# 4_Ethernet_PHY.net
KiCad netlist of a schematic drawn in Altium Designer
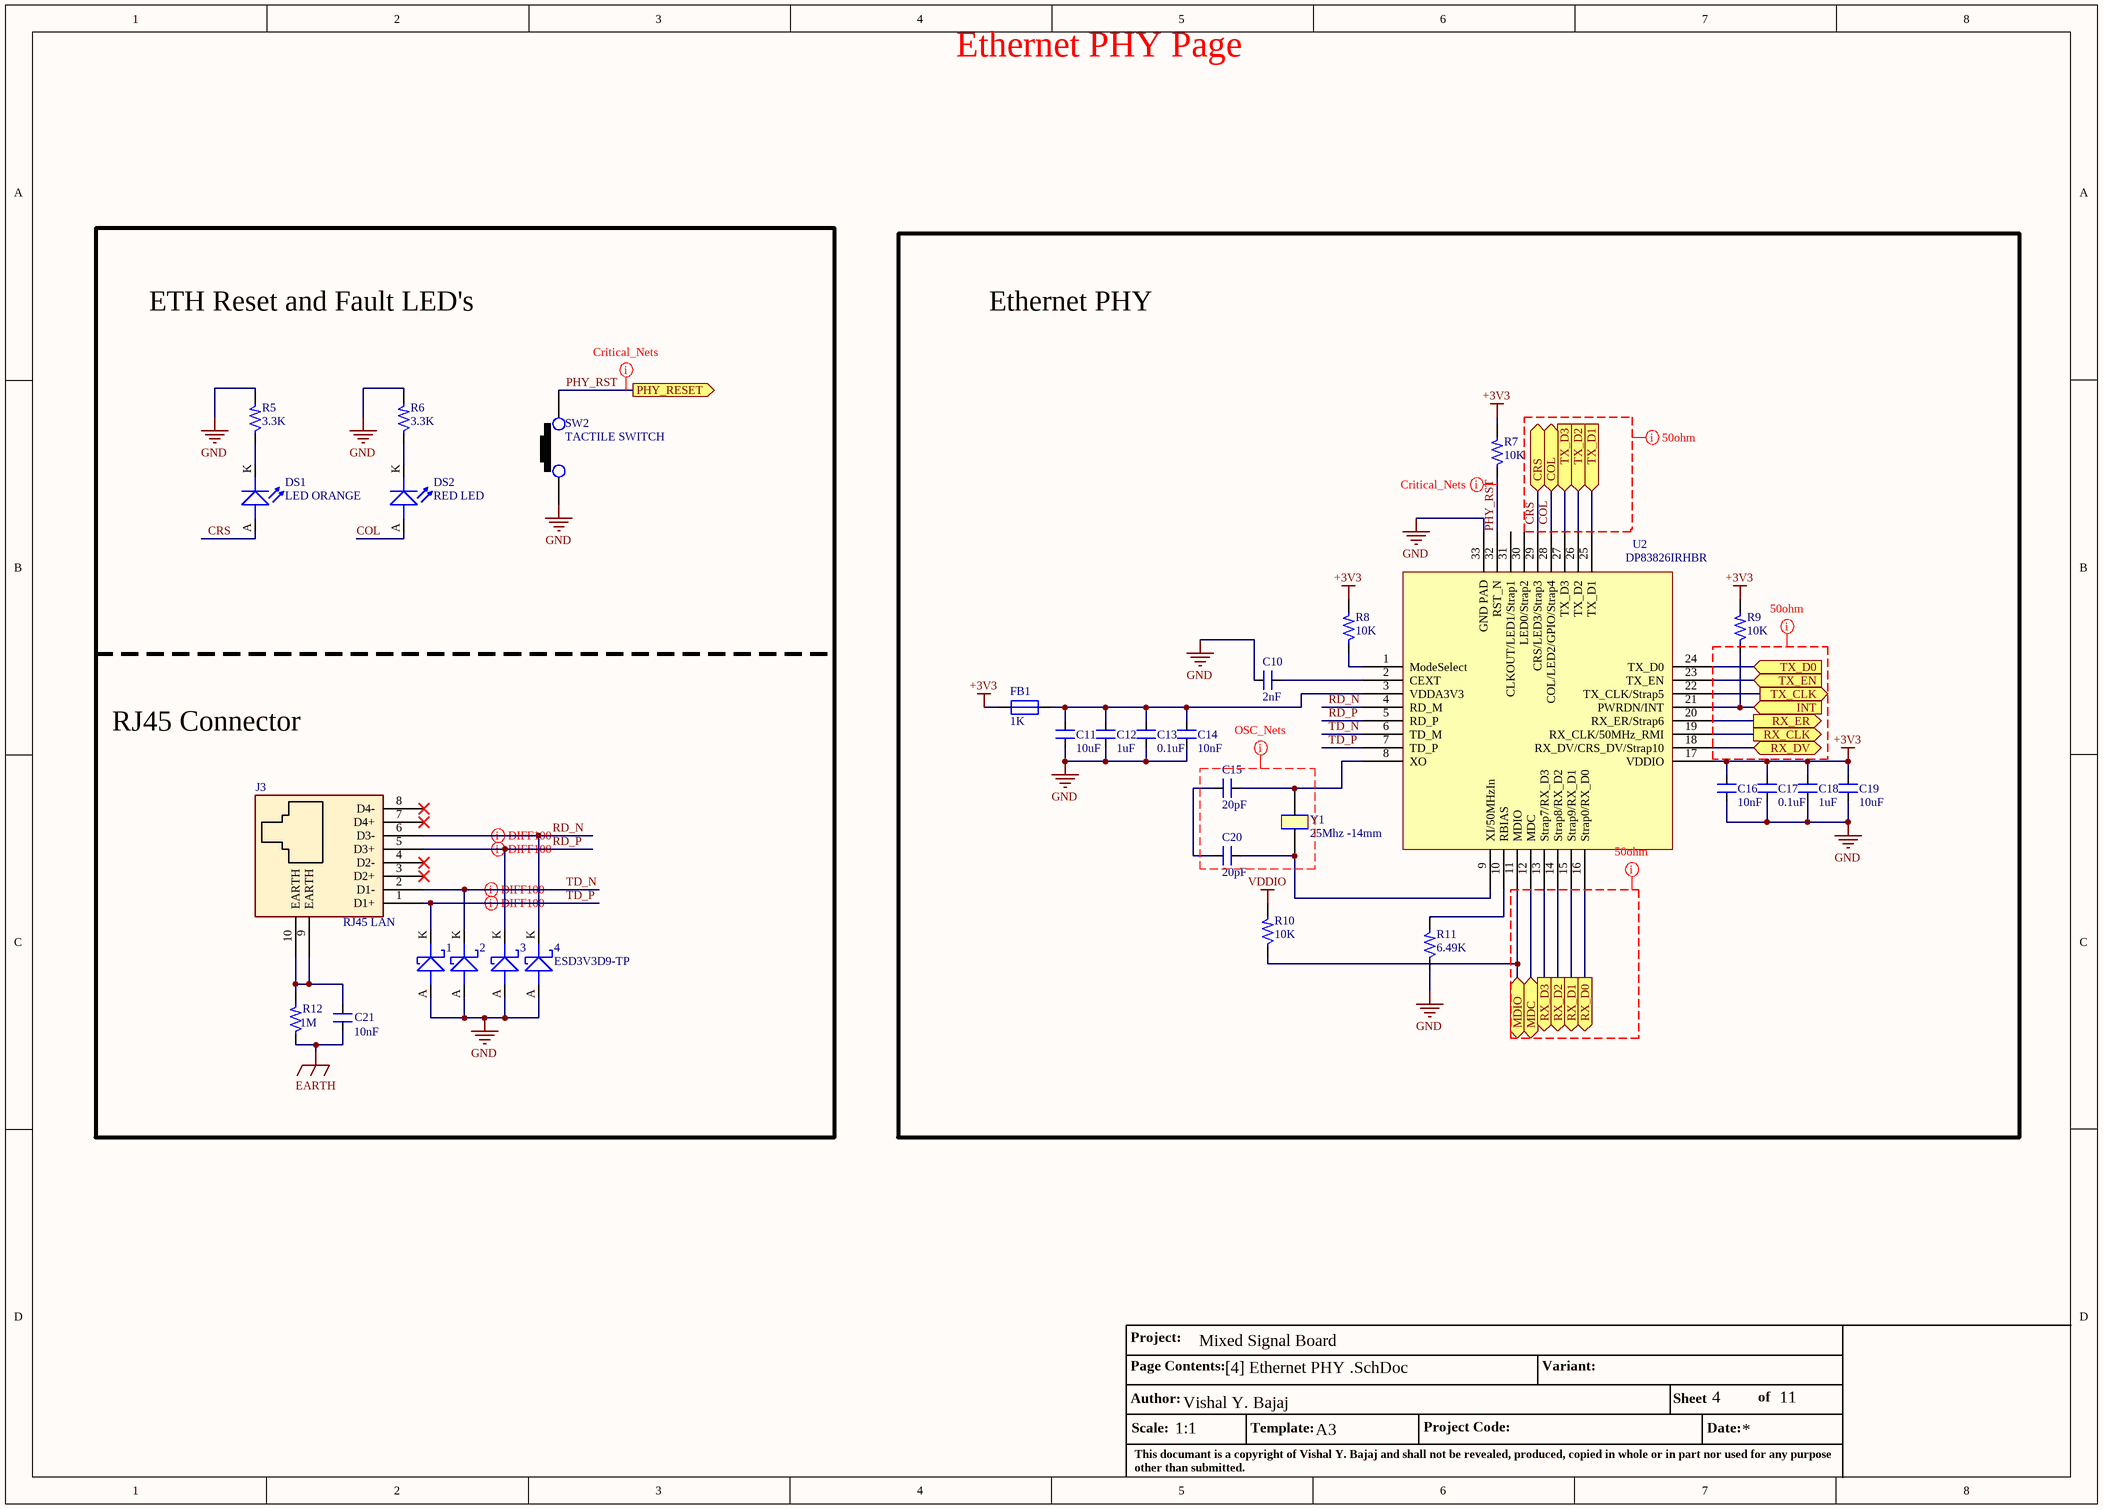
[diagram p0: [4] Ethernet PHY .SchDoc]

(export (version "E")
  (design (tool "Eeschema 10.0.6"))
  (components
    (comp (ref "1")
      (value "ESD3V3D9-TP")
      (footprint "DIO_SOD-923")
      (description "TVS DIODE 3.3V 8.8V SOD923")
      (fields (field (name "MANUFACTURER") "Micro Commercial Co"))
      (libsource (lib "ESTEEMPCBLIB") (part "DIO-T_3.3V-8.8V-10A-SOD923"))
    )
    (comp (ref "2")
      (value "ESD3V3D9-TP")
      (footprint "DIO_SOD-923")
      (description "TVS DIODE 3.3V 8.8V SOD923")
      (fields (field (name "MANUFACTURER") "Micro Commercial Co"))
      (libsource (lib "ESTEEMPCBLIB") (part "DIO-T_3.3V-8.8V-10A-SOD923"))
    )
    (comp (ref "3")
      (value "ESD3V3D9-TP")
      (footprint "DIO_SOD-923")
      (description "TVS DIODE 3.3V 8.8V SOD923")
      (fields (field (name "MANUFACTURER") "Micro Commercial Co"))
      (libsource (lib "ESTEEMPCBLIB") (part "DIO-T_3.3V-8.8V-10A-SOD923"))
    )
    (comp (ref "4")
      (value "ESD3V3D9-TP")
      (footprint "DIO_SOD-923")
      (description "TVS DIODE 3.3V 8.8V SOD923")
      (fields (field (name "MANUFACTURER") "Micro Commercial Co"))
      (libsource (lib "ESTEEMPCBLIB") (part "DIO-T_3.3V-8.8V-10A-SOD923"))
    )
    (comp (ref "C10")
      (value "2nF")
      (footprint "CAP_0805")
      (description "2000pF ±10% 50V Ceramic Capacitor X7R 0805 (2012 Metric)")
      (fields
        (field (name "MANUFACTURER") "Samsung Electro-Mechanics")
        (field (name "MANUFACTURER PART NUMBER") "CL21B202KBANNNC")
      )
      (libsource (lib "ESTEEMPCBLIB") (part "CAP_2nF-50V-10%-0805"))
    )
    (comp (ref "C11")
      (value "10uF")
      (footprint "CAP_1206")
      (description "10µF ±10% 50V Ceramic Capacitor X7R 1206 (3216 Metric)")
      (fields
        (field (name "MANUFACTURER") "KEMET")
        (field (name "MANUFACTURER PART NUMBER") "CL31B106KBHNNNE")
      )
      (libsource (lib "ESTEEMPCBLIB") (part "CAP_10uF-50V-10%-1206"))
    )
    (comp (ref "C12")
      (value "1uF")
      (footprint "CAP_0805")
      (description "1µF ±5% 50V Ceramic Capacitor X7R 0805 (2012 Metric)")
      (fields
        (field (name "MANUFACTURER") "Samsung")
        (field (name "MANUFACTURER PART NUMBER") "CC0805JKX7R9BB105")
      )
      (libsource (lib "ESTEEMPCBLIB") (part "CAP_1uF-50V-5%-0805"))
    )
    (comp (ref "C13")
      (value "0.1uF")
      (footprint "CAP_0805")
      (description "0.1µF ±10% 50V Ceramic Capacitor X7R 0805 (2012 Metric)")
      (fields
        (field (name "MANUFACTURER") "Samsung")
        (field (name "MANUFACTURER PART NUMBER") "CL21B104KBCNNNC")
      )
      (libsource (lib "ESTEEMPCBLIB") (part "CAP_0.1uF-50V-10%-0805"))
    )
    (comp (ref "C14")
      (value "10nF")
      (footprint "CAP_0805")
      (description "10000pF ±10% 50V Ceramic Capacitor X7R 0805 (2012 Metric)")
      (fields
        (field (name "MANUFACTURER") "Samsung")
        (field (name "MANUFACTURER PART NUMBER") "C0805C103K5RECAUTO")
      )
      (libsource (lib "ESTEEMPCBLIB") (part "CAP_10nF-50V-10%-0805"))
    )
    (comp (ref "C15")
      (value "20pF")
      (footprint "CAP_0805")
      (description "±10% 50V Ceramic Capacitor C0G, NP0 0805 (2012 Metric)")
      (fields
        (field (name "MANUFACTURER") "AVX Corporation")
        (field (name "MANUFACTURER PART NUMBER") "08055A200KAT2A")
      )
      (libsource (lib "ESTEEMPCBLIB") (part "CAP_20pF-50V-10%-0805"))
    )
    (comp (ref "C16")
      (value "10nF")
      (footprint "CAP_0805")
      (description "10000pF ±10% 50V Ceramic Capacitor X7R 0805 (2012 Metric)")
      (fields
        (field (name "MANUFACTURER") "Samsung")
        (field (name "MANUFACTURER PART NUMBER") "C0805C103K5RECAUTO")
      )
      (libsource (lib "ESTEEMPCBLIB") (part "CAP_10nF-50V-10%-0805"))
    )
    (comp (ref "C17")
      (value "0.1uF")
      (footprint "CAP_0805")
      (description "0.1µF ±10% 50V Ceramic Capacitor X7R 0805 (2012 Metric)")
      (fields
        (field (name "MANUFACTURER") "Samsung")
        (field (name "MANUFACTURER PART NUMBER") "CL21B104KBCNNNC")
      )
      (libsource (lib "ESTEEMPCBLIB") (part "CAP_0.1uF-50V-10%-0805"))
    )
    (comp (ref "C18")
      (value "1uF")
      (footprint "CAP_0805")
      (description "1µF ±5% 50V Ceramic Capacitor X7R 0805 (2012 Metric)")
      (fields
        (field (name "MANUFACTURER") "Samsung")
        (field (name "MANUFACTURER PART NUMBER") "CC0805JKX7R9BB105")
      )
      (libsource (lib "ESTEEMPCBLIB") (part "CAP_1uF-50V-5%-0805"))
    )
    (comp (ref "C19")
      (value "10uF")
      (footprint "CAP_1206")
      (description "10µF ±10% 50V Ceramic Capacitor X7R 1206 (3216 Metric)")
      (fields
        (field (name "MANUFACTURER") "KEMET")
        (field (name "MANUFACTURER PART NUMBER") "CL31B106KBHNNNE")
      )
      (libsource (lib "ESTEEMPCBLIB") (part "CAP_10uF-50V-10%-1206"))
    )
    (comp (ref "C20")
      (value "20pF")
      (footprint "CAP_0805")
      (description "±10% 50V Ceramic Capacitor C0G, NP0 0805 (2012 Metric)")
      (fields
        (field (name "MANUFACTURER") "AVX Corporation")
        (field (name "MANUFACTURER PART NUMBER") "08055A200KAT2A")
      )
      (libsource (lib "ESTEEMPCBLIB") (part "CAP_20pF-50V-10%-0805"))
    )
    (comp (ref "C21")
      (value "10nF")
      (footprint "CAP_P196_102X287_H332_RAD_TH")
      (description "10000pF ±10% 1000V (1kV) Ceramic Capacitor X7R Radial")
      (fields
        (field (name "MANUFACTURER") "Yageo")
        (field (name "MANUFACTURER PART NUMBER") "RDER73A103K2K1H03B")
      )
      (libsource (lib "ESTEEMPCBLIB") (part "CAP_10nF-1KV-10%-RAD-TH"))
    )
    (comp (ref "DS1")
      (value "LED ORANGE")
      (footprint "LED_0805")
      (description "Orange 605nm LED Indication - Discrete 2V 0805 (2012 Metric)")
      (fields
        (field (name "MANUFACTURER") "Vishay Lite-On")
        (field (name "MANUFACTURER PART NUMBER") "LTST-C170KFKT")
      )
      (libsource (lib "ESTEEMPCBLIB") (part "LED_ORANGE-2V-20mA-0805"))
    )
    (comp (ref "DS2")
      (value "RED LED")
      (footprint "LED_0805")
      (description "Red 631nm LED Indication - Discrete 2V 0805 (2012 Metric)")
      (fields
        (field (name "MANUFACTURER") "Vishay Lite-On")
        (field (name "MANUFACTURER PART NUMBER") "LTST-C171KRKT")
      )
      (libsource (lib "ESTEEMPCBLIB") (part "LED_RED-2V-20mA-0805"))
    )
    (comp (ref "FB1")
      (value "1K")
      (footprint "IND_0805")
      (description "1 kOhms @ 100MHz 1 Power Line Ferrite Bead 0805 (2012 Metric) 1.6A")
      (fields
        (field (name "MANUFACTURER") "Laird")
        (field (name "MANUFACTURER PART NUMBER") "BLM21SP102SH1D")
      )
      (libsource (lib "ESTEEMPCBLIB") (part "FB_1K-100MHZ-1.6A-0805"))
    )
    (comp (ref "J3")
      (value "RJ45 LAN")
      (footprint "CON10_P106_RJ45_TH_ST")
      (description "8 Pins, 2 Row 2.54mm Pitch, right angle Connector, male")
      (fields
        (field (name "MANUFACTURER") "Assmann")
        (field (name "MANUFACTURER PART NUMBER") "A-2004-2-4-LPS-N-R")
      )
      (libsource (lib "ESTEEMPCBLIB") (part "CON-SKT-RJ_8C8P-RA-TH"))
    )
    (comp (ref "R5")
      (value "3.3K")
      (footprint "RES_0805")
      (description "3.3 kOhms ±1% 0.125W, 1/8W Chip Resistor 0805 (2012 Metric) Thick Film")
      (fields (field (name "MANUFACTURER") "Panasonic") (field (name "MANUFACTURER PART NUMBER") "1623214-1"))
      (libsource (lib "ESTEEMPCBLIB") (part "RES_3.3K-0.125W-1%-0805"))
    )
    (comp (ref "R6")
      (value "3.3K")
      (footprint "RES_0805")
      (description "3.3 kOhms ±1% 0.125W, 1/8W Chip Resistor 0805 (2012 Metric) Thick Film")
      (fields (field (name "MANUFACTURER") "Panasonic") (field (name "MANUFACTURER PART NUMBER") "1623214-1"))
      (libsource (lib "ESTEEMPCBLIB") (part "RES_3.3K-0.125W-1%-0805"))
    )
    (comp (ref "R7")
      (value "10K")
      (footprint "RES_0603")
      (description "10 kOhms ±1% 0.1W, 1/10W Chip Resistor 0603 (1608 Metric) Automotive AEC-Q200 Thick Film")
      (fields (field (name "MANUFACTURER") "Walsin") (field (name "MANUFACTURER PART NUMBER") "WR06X1002FTL"))
      (libsource (lib "ESTEEMPCBLIB") (part "RES_10K-0.1W-1%-0603"))
    )
    (comp (ref "R8")
      (value "10K")
      (footprint "RES_0603")
      (description "10 kOhms ±1% 0.1W, 1/10W Chip Resistor 0603 (1608 Metric) Automotive AEC-Q200 Thick Film")
      (fields (field (name "MANUFACTURER") "Walsin") (field (name "MANUFACTURER PART NUMBER") "WR06X1002FTL"))
      (libsource (lib "ESTEEMPCBLIB") (part "RES_10K-0.1W-1%-0603"))
    )
    (comp (ref "R9")
      (value "10K")
      (footprint "RES_0603")
      (description "10 kOhms ±1% 0.1W, 1/10W Chip Resistor 0603 (1608 Metric) Automotive AEC-Q200 Thick Film")
      (fields (field (name "MANUFACTURER") "Walsin") (field (name "MANUFACTURER PART NUMBER") "WR06X1002FTL"))
      (libsource (lib "ESTEEMPCBLIB") (part "RES_10K-0.1W-1%-0603"))
    )
    (comp (ref "R10")
      (value "10K")
      (footprint "RES_0805")
      (description "10 kOhms ±1% 0.125W, 1/8W Chip Resistor 0805 (2012 Metric) Automotive AEC-Q200 Thick Film")
      (fields (field (name "MANUFACTURER") "CTS") (field (name "MANUFACTURER PART NUMBER") "WR08X1002FTL"))
      (libsource (lib "ESTEEMPCBLIB") (part "RES_10K-0.125W-1%-0805"))
    )
    (comp (ref "R11")
      (value "6.49K")
      (footprint "RES_0805")
      (description "6.49 kOhms ±1% 0.125W, 1/8W Chip Resistor 0805 (2012 Metric) Moisture Resistant Thick Film")
      (fields
        (field (name "MANUFACTURER") "Stackpole Electronics")
        (field (name "MANUFACTURER PART NUMBER") "RC0805FR-076K49L")
      )
      (libsource (lib "ESTEEMPCBLIB") (part "RES_6.49K-0.125W-1%-0805"))
    )
    (comp (ref "R12")
      (value "1M")
      (footprint "RES_1206")
      (fields (field (name "MANUFACTURER") "Walsin") (field (name "MANUFACTURER PART NUMBER") "WR12X1004FTL"))
      (libsource (lib "ESTEEMPCBLIB") (part "RES_1M-0.25W-1%-1206"))
    )
    (comp (ref "SW2")
      (value "TACTILE SWITCH")
      (footprint "SW_342_SMD")
      (description "Tactile Switch SPST-NO Top Actuated Surface Mount")
      (fields
        (field (name "MANUFACTURER") "ITT C&K")
        (field (name "MANUFACTURER PART NUMBER") "RS-282G05A3-SMRT")
      )
      (libsource (lib "ESTEEMPCBLIB") (part "SW1_RS-282G05A3-SMRT-SMD"))
    )
    (comp (ref "U2")
      (value "DP83826IRHBR")
      (footprint "VQFN32_19_218_23X9_SMD")
      (fields (field (name "MANUFACTURER") "Texas Instruments"))
      (libsource (lib "ESTEEMPCBLIB") (part "IC_DP83826IRHBR"))
    )
    (comp (ref "Y1")
      (value "25Mhz -14mm")
      (footprint "XTAL_314_240X47_SMD")
      (description "25MHz ±30ppm Crystal 20pF 30 Ohms HC-49/US")
      (fields
        (field (name "MANUFACTURER") "Abracon")
        (field (name "MANUFACTURER PART NUMBER") "FOXSDLF/250F-20")
      )
      (libsource (lib "ESTEEMPCBLIB") (part "XTAL_25Mhz-FOXSDLF/250F-20"))
    )
  )
  (nets
    (net (code "1") (name "+3V3") (class "Default")
      (node (ref "C16") (pin "2") (pinfunction "2_2") (pintype "passive"))
      (node (ref "C17") (pin "2") (pinfunction "2_2") (pintype "passive"))
      (node (ref "C18") (pin "2") (pinfunction "2_2") (pintype "passive"))
      (node (ref "C19") (pin "2") (pinfunction "2_2") (pintype "passive"))
      (node (ref "FB1") (pin "1") (pinfunction "1_1") (pintype "passive"))
      (node (ref "R7") (pin "2") (pinfunction "2_2") (pintype "passive"))
      (node (ref "R8") (pin "2") (pinfunction "2_2") (pintype "passive"))
      (node (ref "R9") (pin "2") (pinfunction "2_2") (pintype "passive"))
      (node (ref "U2") (pin "17") (pinfunction "VDDIO_17") (pintype "passive"))
    )
    (net (code "2") (name "/COL") (class "Default")
      (node (ref "DS2") (pin "A") (pinfunction "ANODE_A") (pintype "passive"))
      (node (ref "U2") (pin "28") (pinfunction "COL/LED2/GPIO/Strap4_28") (pintype "passive"))
    )
    (net (code "3") (name "/CRS") (class "Default")
      (node (ref "DS1") (pin "A") (pinfunction "ANODE_A") (pintype "passive"))
      (node (ref "U2") (pin "29") (pinfunction "CRS/LED3/Strap3_29") (pintype "passive"))
    )
    (net (code "4") (name "/INT") (class "Default")
      (node (ref "R9") (pin "1") (pinfunction "1_1") (pintype "passive"))
      (node (ref "U2") (pin "21") (pinfunction "PWRDN/INT_21") (pintype "passive"))
    )
    (net (code "5") (name "/MDC") (class "Default")
      (node (ref "U2") (pin "12") (pinfunction "MDC_12") (pintype "passive"))
    )
    (net (code "6") (name "/MDIO") (class "Default")
      (node (ref "R10") (pin "1") (pinfunction "1_1") (pintype "passive"))
      (node (ref "U2") (pin "11") (pinfunction "MDIO_11") (pintype "passive"))
    )
    (net (code "7") (name "/PHY_RST") (class "Default")
      (node (ref "R7") (pin "1") (pinfunction "1_1") (pintype "passive"))
      (node (ref "SW2") (pin "2") (pinfunction "2_2") (pintype "passive"))
      (node (ref "U2") (pin "32") (pinfunction "RST_N_32") (pintype "passive"))
    )
    (net (code "8") (name "/RD_N") (class "Default")
      (node (ref "4") (pin "K") (pinfunction "K_K") (pintype "passive"))
      (node (ref "J3") (pin "6") (pinfunction "D3-_6") (pintype "passive"))
      (node (ref "U2") (pin "4") (pinfunction "RD_M_4") (pintype "passive"))
    )
    (net (code "9") (name "/RD_P") (class "Default")
      (node (ref "3") (pin "K") (pinfunction "K_K") (pintype "passive"))
      (node (ref "J3") (pin "5") (pinfunction "D3+_5") (pintype "passive"))
      (node (ref "U2") (pin "5") (pinfunction "RD_P_5") (pintype "passive"))
    )
    (net (code "10") (name "/RX_CLK") (class "Default")
      (node (ref "U2") (pin "19") (pinfunction "RX_CLK/50MHz_RMI_19") (pintype "passive"))
    )
    (net (code "11") (name "/RX_D0") (class "Default")
      (node (ref "U2") (pin "16") (pinfunction "Strap0/RX_D0_16") (pintype "passive"))
    )
    (net (code "12") (name "/RX_D1") (class "Default")
      (node (ref "U2") (pin "15") (pinfunction "Strap9/RX_D1_15") (pintype "passive"))
    )
    (net (code "13") (name "/RX_D2") (class "Default")
      (node (ref "U2") (pin "14") (pinfunction "Strap8/RX_D2_14") (pintype "passive"))
    )
    (net (code "14") (name "/RX_D3") (class "Default")
      (node (ref "U2") (pin "13") (pinfunction "Strap7/RX_D3_13") (pintype "passive"))
    )
    (net (code "15") (name "/RX_DV") (class "Default")
      (node (ref "U2") (pin "18") (pinfunction "RX_DV/CRS_DV/Strap10_18") (pintype "passive"))
    )
    (net (code "16") (name "/RX_ER") (class "Default")
      (node (ref "U2") (pin "20") (pinfunction "RX_ER/Strap6_20") (pintype "passive"))
    )
    (net (code "17") (name "/TD_N") (class "Default")
      (node (ref "2") (pin "K") (pinfunction "K_K") (pintype "passive"))
      (node (ref "J3") (pin "2") (pinfunction "D1-_2") (pintype "passive"))
      (node (ref "U2") (pin "6") (pinfunction "TD_M_6") (pintype "passive"))
    )
    (net (code "18") (name "/TD_P") (class "Default")
      (node (ref "1") (pin "K") (pinfunction "K_K") (pintype "passive"))
      (node (ref "J3") (pin "1") (pinfunction "D1+_1") (pintype "passive"))
      (node (ref "U2") (pin "7") (pinfunction "TD_P_7") (pintype "passive"))
    )
    (net (code "19") (name "/TX_CLK") (class "Default")
      (node (ref "U2") (pin "22") (pinfunction "TX_CLK/Strap5_22") (pintype "passive"))
    )
    (net (code "20") (name "/TX_D0") (class "Default")
      (node (ref "U2") (pin "24") (pinfunction "TX_D0_24") (pintype "passive"))
    )
    (net (code "21") (name "/TX_D1") (class "Default")
      (node (ref "U2") (pin "25") (pinfunction "TX_D1_25") (pintype "passive"))
    )
    (net (code "22") (name "/TX_D2") (class "Default")
      (node (ref "U2") (pin "26") (pinfunction "TX_D2_26") (pintype "passive"))
    )
    (net (code "23") (name "/TX_D3") (class "Default")
      (node (ref "U2") (pin "27") (pinfunction "TX_D3_27") (pintype "passive"))
    )
    (net (code "24") (name "/TX_EN") (class "Default")
      (node (ref "U2") (pin "23") (pinfunction "TX_EN_23") (pintype "passive"))
    )
    (net (code "25") (name "EARTH") (class "Default")
      (node (ref "C21") (pin "1") (pinfunction "1_1") (pintype "passive"))
      (node (ref "R12") (pin "1") (pinfunction "1_1") (pintype "passive"))
    )
    (net (code "26") (name "GND") (class "Default")
      (node (ref "1") (pin "A") (pinfunction "A_A") (pintype "passive"))
      (node (ref "2") (pin "A") (pinfunction "A_A") (pintype "passive"))
      (node (ref "3") (pin "A") (pinfunction "A_A") (pintype "passive"))
      (node (ref "4") (pin "A") (pinfunction "A_A") (pintype "passive"))
      (node (ref "C10") (pin "1") (pinfunction "1_1") (pintype "passive"))
      (node (ref "C11") (pin "1") (pinfunction "1_1") (pintype "passive"))
      (node (ref "C12") (pin "1") (pinfunction "1_1") (pintype "passive"))
      (node (ref "C13") (pin "1") (pinfunction "1_1") (pintype "passive"))
      (node (ref "C14") (pin "1") (pinfunction "1_1") (pintype "passive"))
      (node (ref "C16") (pin "1") (pinfunction "1_1") (pintype "passive"))
      (node (ref "C17") (pin "1") (pinfunction "1_1") (pintype "passive"))
      (node (ref "C18") (pin "1") (pinfunction "1_1") (pintype "passive"))
      (node (ref "C19") (pin "1") (pinfunction "1_1") (pintype "passive"))
      (node (ref "R11") (pin "1") (pinfunction "1_1") (pintype "passive"))
      (node (ref "R5") (pin "2") (pinfunction "2_2") (pintype "passive"))
      (node (ref "R6") (pin "2") (pinfunction "2_2") (pintype "passive"))
      (node (ref "SW2") (pin "1") (pinfunction "1_1") (pintype "passive"))
      (node (ref "U2") (pin "33") (pinfunction "GND_PAD_33") (pintype "passive"))
    )
    (net (code "27") (name "Net-(C15-Pad2)") (class "Default")
      (node (ref "C15") (pin "2") (pinfunction "2_2") (pintype "passive"))
      (node (ref "C20") (pin "2") (pinfunction "2_2") (pintype "passive"))
    )
    (net (code "28") (name "Net-(C21-Pad2)") (class "Default")
      (node (ref "C21") (pin "2") (pinfunction "2_2") (pintype "passive"))
      (node (ref "J3") (pin "10") (pinfunction "EARTH_10") (pintype "passive"))
      (node (ref "J3") (pin "9") (pinfunction "EARTH_9") (pintype "passive"))
      (node (ref "R12") (pin "2") (pinfunction "2_2") (pintype "passive"))
    )
    (net (code "29") (name "Net-(DS1-CATHODE)") (class "Default")
      (node (ref "DS1") (pin "K") (pinfunction "CATHODE_K") (pintype "passive"))
      (node (ref "R5") (pin "1") (pinfunction "1_1") (pintype "passive"))
    )
    (net (code "30") (name "Net-(DS2-CATHODE)") (class "Default")
      (node (ref "DS2") (pin "K") (pinfunction "CATHODE_K") (pintype "passive"))
      (node (ref "R6") (pin "1") (pinfunction "1_1") (pintype "passive"))
    )
    (net (code "31") (name "Net-(U2-CEXT)") (class "Default")
      (node (ref "C10") (pin "2") (pinfunction "2_2") (pintype "passive"))
      (node (ref "U2") (pin "2") (pinfunction "CEXT_2") (pintype "passive"))
    )
    (net (code "32") (name "Net-(U2-ModeSelect)") (class "Default")
      (node (ref "R8") (pin "1") (pinfunction "1_1") (pintype "passive"))
      (node (ref "U2") (pin "1") (pinfunction "ModeSelect_1") (pintype "passive"))
    )
    (net (code "33") (name "Net-(U2-RBIAS)") (class "Default")
      (node (ref "R11") (pin "2") (pinfunction "2_2") (pintype "passive"))
      (node (ref "U2") (pin "10") (pinfunction "RBIAS_10") (pintype "passive"))
    )
    (net (code "34") (name "Net-(U2-VDDA3V3)") (class "Default")
      (node (ref "C11") (pin "2") (pinfunction "2_2") (pintype "passive"))
      (node (ref "C12") (pin "2") (pinfunction "2_2") (pintype "passive"))
      (node (ref "C13") (pin "2") (pinfunction "2_2") (pintype "passive"))
      (node (ref "C14") (pin "2") (pinfunction "2_2") (pintype "passive"))
      (node (ref "FB1") (pin "2") (pinfunction "2_2") (pintype "passive"))
      (node (ref "U2") (pin "3") (pinfunction "VDDA3V3_3") (pintype "passive"))
    )
    (net (code "35") (name "Net-(U2-XI{slash}50MHzIn)") (class "Default")
      (node (ref "C20") (pin "1") (pinfunction "1_1") (pintype "passive"))
      (node (ref "U2") (pin "9") (pinfunction "XI/50MHzIn_9") (pintype "passive"))
      (node (ref "Y1") (pin "1") (pinfunction "1_1") (pintype "passive"))
    )
    (net (code "36") (name "Net-(U2-XO)") (class "Default")
      (node (ref "C15") (pin "1") (pinfunction "1_1") (pintype "passive"))
      (node (ref "U2") (pin "8") (pinfunction "XO_8") (pintype "passive"))
      (node (ref "Y1") (pin "2") (pinfunction "2_2") (pintype "passive"))
    )
    (net (code "37") (name "VDDIO") (class "Default")
      (node (ref "R10") (pin "2") (pinfunction "2_2") (pintype "passive"))
    )
    (net (code "38") (name "unconnected-(J3-D2+-Pad3)") (class "Default")
      (node (ref "J3") (pin "3") (pinfunction "D2+_3") (pintype "passive+no_connect"))
    )
    (net (code "39") (name "unconnected-(J3-D2--Pad4)") (class "Default")
      (node (ref "J3") (pin "4") (pinfunction "D2-_4") (pintype "passive+no_connect"))
    )
    (net (code "40") (name "unconnected-(J3-D4+-Pad7)") (class "Default")
      (node (ref "J3") (pin "7") (pinfunction "D4+_7") (pintype "passive+no_connect"))
    )
    (net (code "41") (name "unconnected-(J3-D4--Pad8)") (class "Default")
      (node (ref "J3") (pin "8") (pinfunction "D4-_8") (pintype "passive+no_connect"))
    )
    (net (code "42") (name "unconnected-(U2-CLKOUT{slash}LED1{slash}Strap1-Pad31)") (class "Default")
      (node (ref "U2") (pin "31") (pinfunction "CLKOUT/LED1/Strap1_31") (pintype "passive"))
    )
    (net (code "43") (name "unconnected-(U2-LED0{slash}Strap2-Pad30)") (class "Default")
      (node (ref "U2") (pin "30") (pinfunction "LED0/Strap2_30") (pintype "passive"))
    )
  )
)
